# XenoGC-mini.net
KiCad netlist of a schematic drawn in EAGLE
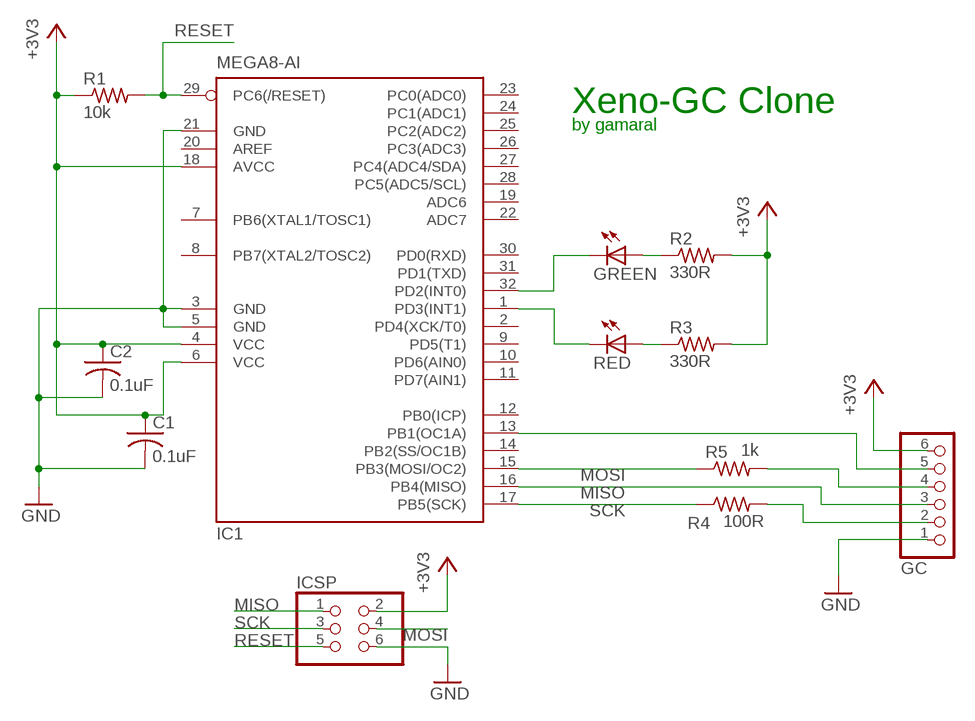
[diagram p0: schematic, sheet 1]

(export (version "E")
  (design (tool "Eeschema 10.0.6"))
  (components
    (comp (ref "C1")
      (value "0.1uF")
      (footprint "eagle-import:C0805K")
      (libsource (lib "eagle-import") (part "C-USC0805K"))
    )
    (comp (ref "C2")
      (value "0.1uF")
      (footprint "eagle-import:C0805K")
      (libsource (lib "eagle-import") (part "C-USC0805K"))
    )
    (comp (ref "GC")
      (value "PINHD-1X6/90")
      (footprint "eagle-import:1X06_90")
      (libsource (lib "eagle-import") (part "PINHD-1X6/90"))
    )
    (comp (ref "GREEN")
      (value "LEDSML1206")
      (footprint "eagle-import:SML1206")
      (libsource (lib "eagle-import") (part "LEDSML1206"))
    )
    (comp (ref "IC1")
      (value "MEGA8-AI")
      (footprint "eagle-import:TQFP32-08")
      (fields (field (name "MPN") "ATMEGA8-16AU"))
      (libsource (lib "eagle-import") (part "MEGA8-AI"))
    )
    (comp (ref "ICSP")
      (value "PINHD-2X3")
      (footprint "eagle-import:2X03")
      (libsource (lib "eagle-import") (part "PINHD-2X3"))
    )
    (comp (ref "R1")
      (value "10k")
      (footprint "eagle-import:R0805W")
      (libsource (lib "eagle-import") (part "R-US_R0805W"))
    )
    (comp (ref "R2")
      (value "330R")
      (footprint "eagle-import:R0805W")
      (libsource (lib "eagle-import") (part "R-US_R0805W"))
    )
    (comp (ref "R3")
      (value "330R")
      (footprint "eagle-import:R0805W")
      (libsource (lib "eagle-import") (part "R-US_R0805W"))
    )
    (comp (ref "R4")
      (value "100R")
      (footprint "eagle-import:R0805W")
      (libsource (lib "eagle-import") (part "R-US_R0805W"))
    )
    (comp (ref "R5")
      (value "1k")
      (footprint "eagle-import:R0805W")
      (libsource (lib "eagle-import") (part "R-US_R0805W"))
    )
    (comp (ref "RED")
      (value "LEDSML1206")
      (footprint "eagle-import:SML1206")
      (libsource (lib "eagle-import") (part "LEDSML1206"))
    )
  )
  (nets
    (net (code "1") (name "+3V3") (class "Default")
      (node (ref "C1") (pin "1") (pinfunction "1_1") (pintype "passive"))
      (node (ref "C2") (pin "1") (pinfunction "1_1") (pintype "passive"))
      (node (ref "GC") (pin "6") (pinfunction "6_6") (pintype "passive"))
      (node (ref "IC1") (pin "18") (pinfunction "AVCC_18") (pintype "power_in"))
      (node (ref "IC1") (pin "4") (pinfunction "VCC_4") (pintype "power_in"))
      (node (ref "IC1") (pin "6") (pinfunction "VCC_6") (pintype "power_in"))
      (node (ref "ICSP") (pin "2") (pinfunction "2_2") (pintype "passive"))
      (node (ref "R1") (pin "1") (pinfunction "1_1") (pintype "passive"))
      (node (ref "R2") (pin "2") (pinfunction "2_2") (pintype "passive"))
      (node (ref "R3") (pin "2") (pinfunction "2_2") (pintype "passive"))
    )
    (net (code "2") (name "/MISO") (class "Default")
      (node (ref "GC") (pin "3") (pinfunction "3_3") (pintype "passive"))
      (node (ref "IC1") (pin "16") (pinfunction "PB4(MISO)_16") (pintype "bidirectional"))
      (node (ref "ICSP") (pin "1") (pinfunction "1_1") (pintype "passive"))
    )
    (net (code "3") (name "/MOSI") (class "Default")
      (node (ref "IC1") (pin "15") (pinfunction "PB3(MOSI/OC2)_15") (pintype "bidirectional"))
      (node (ref "ICSP") (pin "4") (pinfunction "4_4") (pintype "passive"))
      (node (ref "R5") (pin "1") (pinfunction "1_1") (pintype "passive"))
    )
    (net (code "4") (name "/RESET") (class "Default")
      (node (ref "IC1") (pin "29") (pinfunction "PC6(/RESET)_29") (pintype "bidirectional"))
      (node (ref "ICSP") (pin "5") (pinfunction "5_5") (pintype "passive"))
      (node (ref "R1") (pin "2") (pinfunction "2_2") (pintype "passive"))
    )
    (net (code "5") (name "/SCK") (class "Default")
      (node (ref "IC1") (pin "17") (pinfunction "PB5(SCK)_17") (pintype "bidirectional"))
      (node (ref "ICSP") (pin "3") (pinfunction "3_3") (pintype "passive"))
      (node (ref "R4") (pin "1") (pinfunction "1_1") (pintype "passive"))
    )
    (net (code "6") (name "GND") (class "Default")
      (node (ref "C1") (pin "2") (pinfunction "2_2") (pintype "passive"))
      (node (ref "C2") (pin "2") (pinfunction "2_2") (pintype "passive"))
      (node (ref "GC") (pin "1") (pinfunction "1_1") (pintype "passive"))
      (node (ref "IC1") (pin "21") (pinfunction "GND_21") (pintype "power_in"))
      (node (ref "IC1") (pin "3") (pinfunction "GND_3") (pintype "power_in"))
      (node (ref "IC1") (pin "5") (pinfunction "GND_5") (pintype "power_in"))
      (node (ref "ICSP") (pin "6") (pinfunction "6_6") (pintype "passive"))
    )
    (net (code "7") (name "Net-(GC-Pad2)") (class "Default")
      (node (ref "GC") (pin "2") (pinfunction "2_2") (pintype "passive"))
      (node (ref "R4") (pin "2") (pinfunction "2_2") (pintype "passive"))
    )
    (net (code "8") (name "Net-(GC-Pad4)") (class "Default")
      (node (ref "GC") (pin "4") (pinfunction "4_4") (pintype "passive"))
      (node (ref "R5") (pin "2") (pinfunction "2_2") (pintype "passive"))
    )
    (net (code "9") (name "Net-(GREEN-PadA)") (class "Default")
      (node (ref "GREEN") (pin "A") (pinfunction "A_A") (pintype "passive"))
      (node (ref "R2") (pin "1") (pinfunction "1_1") (pintype "passive"))
    )
    (net (code "10") (name "Net-(IC1-PB1(OC1A))") (class "Default")
      (node (ref "GC") (pin "5") (pinfunction "5_5") (pintype "passive"))
      (node (ref "IC1") (pin "13") (pinfunction "PB1(OC1A)_13") (pintype "bidirectional"))
    )
    (net (code "11") (name "Net-(IC1-PD2(INT0))") (class "Default")
      (node (ref "GREEN") (pin "C") (pinfunction "C_C") (pintype "passive"))
      (node (ref "IC1") (pin "32") (pinfunction "PD2(INT0)_32") (pintype "bidirectional"))
    )
    (net (code "12") (name "Net-(IC1-PD3(INT1))") (class "Default")
      (node (ref "IC1") (pin "1") (pinfunction "PD3(INT1)_1") (pintype "bidirectional"))
      (node (ref "RED") (pin "C") (pinfunction "C_C") (pintype "passive"))
    )
    (net (code "13") (name "Net-(R3-Pad1)") (class "Default")
      (node (ref "R3") (pin "1") (pinfunction "1_1") (pintype "passive"))
      (node (ref "RED") (pin "A") (pinfunction "A_A") (pintype "passive"))
    )
    (net (code "14") (name "unconnected-(IC1-ADC6-Pad19)") (class "Default")
      (node (ref "IC1") (pin "19") (pinfunction "ADC6_19") (pintype "bidirectional"))
    )
    (net (code "15") (name "unconnected-(IC1-ADC7-Pad22)") (class "Default")
      (node (ref "IC1") (pin "22") (pinfunction "ADC7_22") (pintype "bidirectional"))
    )
    (net (code "16") (name "unconnected-(IC1-AREF-Pad20)") (class "Default")
      (node (ref "IC1") (pin "20") (pinfunction "AREF_20") (pintype "passive"))
    )
    (net (code "17") (name "unconnected-(IC1-PB0(ICP)-Pad12)") (class "Default")
      (node (ref "IC1") (pin "12") (pinfunction "PB0(ICP)_12") (pintype "bidirectional"))
    )
    (net (code "18") (name "unconnected-(IC1-PB2(SS{slash}OC1B)-Pad14)") (class "Default")
      (node (ref "IC1") (pin "14") (pinfunction "PB2(SS/OC1B)_14") (pintype "bidirectional"))
    )
    (net (code "19") (name "unconnected-(IC1-PB6(XTAL1{slash}TOSC1)-Pad7)") (class "Default")
      (node (ref "IC1") (pin "7") (pinfunction "PB6(XTAL1/TOSC1)_7") (pintype "bidirectional"))
    )
    (net (code "20") (name "unconnected-(IC1-PB7(XTAL2{slash}TOSC2)-Pad8)") (class "Default")
      (node (ref "IC1") (pin "8") (pinfunction "PB7(XTAL2/TOSC2)_8") (pintype "bidirectional"))
    )
    (net (code "21") (name "unconnected-(IC1-PC0(ADC0)-Pad23)") (class "Default")
      (node (ref "IC1") (pin "23") (pinfunction "PC0(ADC0)_23") (pintype "bidirectional"))
    )
    (net (code "22") (name "unconnected-(IC1-PC1(ADC1)-Pad24)") (class "Default")
      (node (ref "IC1") (pin "24") (pinfunction "PC1(ADC1)_24") (pintype "bidirectional"))
    )
    (net (code "23") (name "unconnected-(IC1-PC2(ADC2)-Pad25)") (class "Default")
      (node (ref "IC1") (pin "25") (pinfunction "PC2(ADC2)_25") (pintype "bidirectional"))
    )
    (net (code "24") (name "unconnected-(IC1-PC3(ADC3)-Pad26)") (class "Default")
      (node (ref "IC1") (pin "26") (pinfunction "PC3(ADC3)_26") (pintype "bidirectional"))
    )
    (net (code "25") (name "unconnected-(IC1-PC4(ADC4{slash}SDA)-Pad27)") (class "Default")
      (node (ref "IC1") (pin "27") (pinfunction "PC4(ADC4/SDA)_27") (pintype "bidirectional"))
    )
    (net (code "26") (name "unconnected-(IC1-PC5(ADC5{slash}SCL)-Pad28)") (class "Default")
      (node (ref "IC1") (pin "28") (pinfunction "PC5(ADC5/SCL)_28") (pintype "bidirectional"))
    )
    (net (code "27") (name "unconnected-(IC1-PD0(RXD)-Pad30)") (class "Default")
      (node (ref "IC1") (pin "30") (pinfunction "PD0(RXD)_30") (pintype "bidirectional"))
    )
    (net (code "28") (name "unconnected-(IC1-PD1(TXD)-Pad31)") (class "Default")
      (node (ref "IC1") (pin "31") (pinfunction "PD1(TXD)_31") (pintype "bidirectional"))
    )
    (net (code "29") (name "unconnected-(IC1-PD4(XCK{slash}T0)-Pad2)") (class "Default")
      (node (ref "IC1") (pin "2") (pinfunction "PD4(XCK/T0)_2") (pintype "bidirectional"))
    )
    (net (code "30") (name "unconnected-(IC1-PD5(T1)-Pad9)") (class "Default")
      (node (ref "IC1") (pin "9") (pinfunction "PD5(T1)_9") (pintype "bidirectional"))
    )
    (net (code "31") (name "unconnected-(IC1-PD6(AIN0)-Pad10)") (class "Default")
      (node (ref "IC1") (pin "10") (pinfunction "PD6(AIN0)_10") (pintype "bidirectional"))
    )
    (net (code "32") (name "unconnected-(IC1-PD7(AIN1)-Pad11)") (class "Default")
      (node (ref "IC1") (pin "11") (pinfunction "PD7(AIN1)_11") (pintype "bidirectional"))
    )
  )
)
